# SmokeDetector.net
KiCad netlist of a schematic drawn in Altium Designer
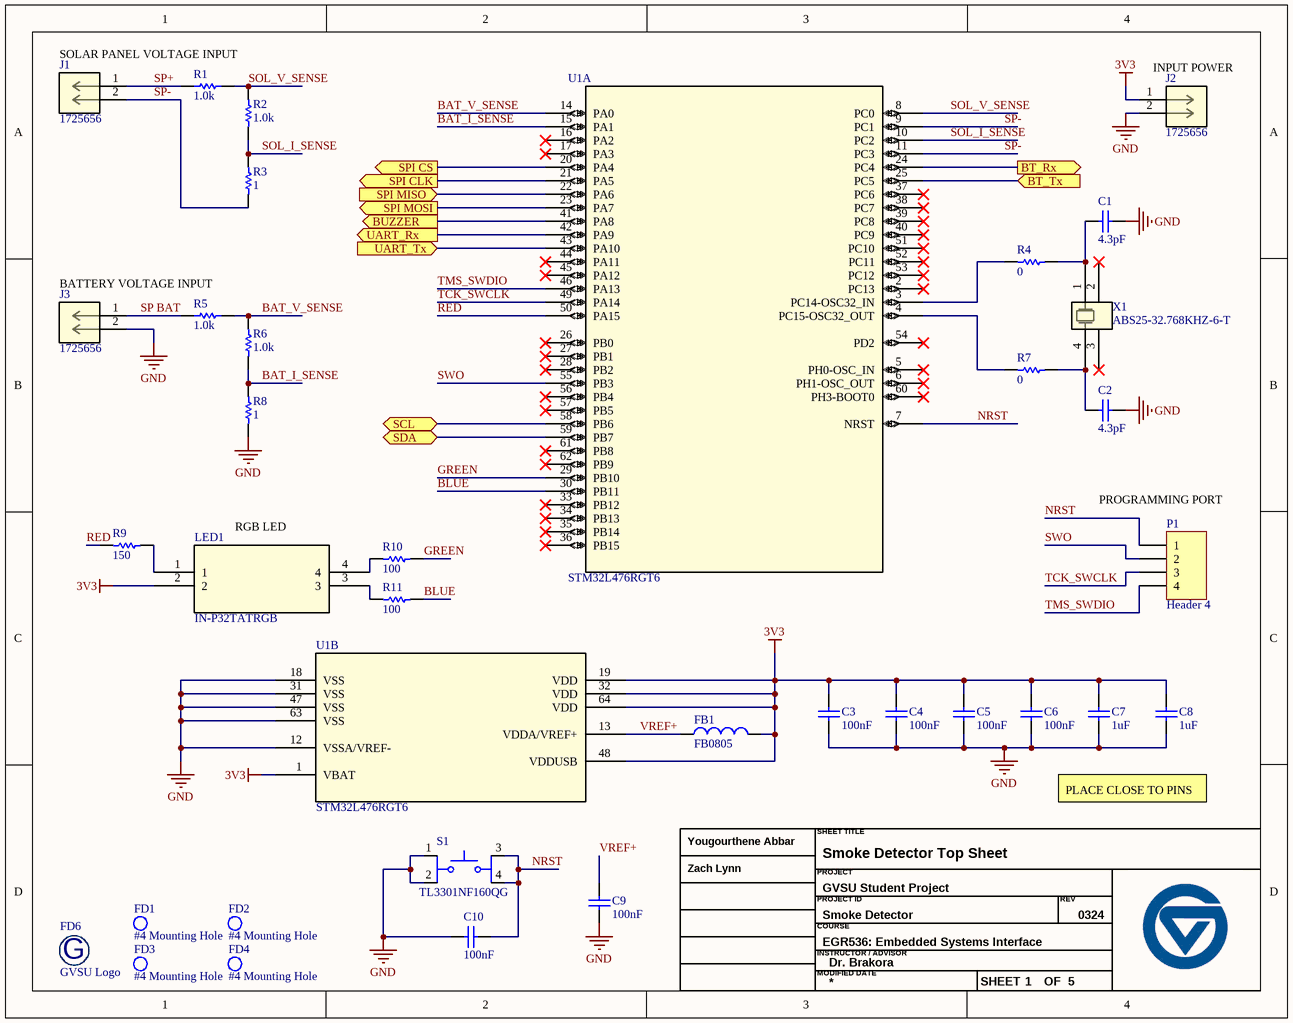
[diagram p0: SmokeDetector.SchDoc]

(export (version "E")
  (design (tool "Eeschema 10.0.6"))
  (components
    (comp (ref "C1")
      (value "4.3pF")
      (footprint "0402cap")
      (description "0402 Ceramic Chip Capacitor - Standard")
      (fields (field (name "Comment") "C0402"))
      (libsource (lib "Standard Components") (part "C0402"))
    )
    (comp (ref "C2")
      (value "4.3pF")
      (footprint "0402cap")
      (description "0402 Ceramic Chip Capacitor - Standard")
      (fields (field (name "Comment") "C0402"))
      (libsource (lib "Standard Components") (part "C0402"))
    )
    (comp (ref "C3")
      (value "100nF")
      (footprint "0402cap")
      (description "0402 Ceramic Chip Capacitor - Standard")
      (fields (field (name "Comment") "C0402"))
      (libsource (lib "Standard Components") (part "C0402"))
    )
    (comp (ref "C4")
      (value "100nF")
      (footprint "0402cap")
      (description "0402 Ceramic Chip Capacitor - Standard")
      (fields (field (name "Comment") "C0402"))
      (libsource (lib "Standard Components") (part "C0402"))
    )
    (comp (ref "C5")
      (value "100nF")
      (footprint "0402cap")
      (description "0402 Ceramic Chip Capacitor - Standard")
      (fields (field (name "Comment") "C0402"))
      (libsource (lib "Standard Components") (part "C0402"))
    )
    (comp (ref "C6")
      (value "100nF")
      (footprint "0402cap")
      (description "0402 Ceramic Chip Capacitor - Standard")
      (fields (field (name "Comment") "C0402"))
      (libsource (lib "Standard Components") (part "C0402"))
    )
    (comp (ref "C7")
      (value "1uF")
      (footprint "0402cap")
      (description "0402 Ceramic Chip Capacitor - Standard")
      (fields (field (name "Comment") "C0402"))
      (libsource (lib "Standard Components") (part "C0402"))
    )
    (comp (ref "C8")
      (value "1uF")
      (footprint "0805CAP")
      (description "0805 Ceramic Chip Capacitor - Standard")
      (fields (field (name "Comment") "C0805"))
      (libsource (lib "Standard Components") (part "C0805"))
    )
    (comp (ref "C9")
      (value "100nF")
      (footprint "0402cap")
      (description "0402 Ceramic Chip Capacitor - Standard")
      (fields (field (name "Comment") "C0402"))
      (libsource (lib "Standard Components") (part "C0402"))
    )
    (comp (ref "C10")
      (value "100nF")
      (footprint "0402cap")
      (description "0402 Ceramic Chip Capacitor - Standard")
      (fields (field (name "Comment") "C0402"))
      (libsource (lib "Standard Components") (part "C0402"))
    )
    (comp (ref "FB1")
      (value "FB0805")
      (footprint "0805CAP")
      (description "0805 Multilayer Ferrite Power Bead")
      (fields (field (name "MANUFACTURER") "KOA Speer"))
      (libsource (lib "Standard Components") (part "FB0805"))
    )
    (comp (ref "FD1")
      (value "#4 Mounting Hole")
      (footprint "#4 Mounting Hole-Footprint-1")
      (description "#4 clearance hole, unplated.")
      (libsource (lib "Standard Components") (part "#4 Mounting Hole"))
    )
    (comp (ref "FD2")
      (value "#4 Mounting Hole")
      (footprint "#4 Mounting Hole-Footprint-1")
      (description "#4 clearance hole, unplated.")
      (libsource (lib "Standard Components") (part "#4 Mounting Hole"))
    )
    (comp (ref "FD3")
      (value "#4 Mounting Hole")
      (footprint "#4 Mounting Hole-Footprint-1")
      (description "#4 clearance hole, unplated.")
      (libsource (lib "Standard Components") (part "#4 Mounting Hole"))
    )
    (comp (ref "FD4")
      (value "#4 Mounting Hole")
      (footprint "#4 Mounting Hole-Footprint-1")
      (description "#4 clearance hole, unplated.")
      (libsource (lib "Standard Components") (part "#4 Mounting Hole"))
    )
    (comp (ref "FD6")
      (value "GVSU Logo")
      (footprint "GVSU Symbol Only")
      (description "GVSU Logo (Several Symbols)")
      (libsource (lib "Standard Components") (part "GVSU Logo"))
    )
    (comp (ref "J1")
      (value "1725656")
      (footprint "CONN_1725656_PXC")
      (description "No Description Available")
      (libsource (lib "") (part "1725656_1"))
    )
    (comp (ref "J2")
      (value "1725656")
      (footprint "CONN_1725656_PXC")
      (description "No Description Available")
      (libsource (lib "ScrewTerminal2Position") (part "1725656"))
    )
    (comp (ref "J3")
      (value "1725656")
      (footprint "CONN_1725656_PXC")
      (description "No Description Available")
      (libsource (lib "") (part "1725656_1"))
    )
    (comp (ref "LED1")
      (value "IN-P32TATRGB")
      (footprint "4-PLCC_3P2X2P8_INL")
      (description "No Description Available")
      (libsource (lib "RGB") (part "IN-P32TATRGB"))
    )
    (comp (ref "P1")
      (value "Header 4")
      (footprint "HDR1X4")
      (description "Header, 4-Pin")
      (fields (field (name "PUBLISHER") "Altium Limited"))
      (libsource (lib "Miscellaneous Connectors") (part "Header 4"))
    )
    (comp (ref "R1")
      (value "1.0k")
      (footprint "0805RES")
      (description "0805 Chip Resistor - Standard")
      (fields (field (name "Comment") "R0805"))
      (libsource (lib "Standard Components") (part "R0805"))
    )
    (comp (ref "R2")
      (value "1.0k")
      (footprint "0805RES")
      (description "0805 Chip Resistor - Standard")
      (fields (field (name "Comment") "R0805"))
      (libsource (lib "Standard Components") (part "R0805"))
    )
    (comp (ref "R3")
      (value "1")
      (footprint "0805RES")
      (description "0805 Chip Resistor - Standard")
      (fields (field (name "Comment") "R0805"))
      (libsource (lib "Standard Components") (part "R0805"))
    )
    (comp (ref "R4")
      (value "0")
      (footprint "0402RES")
      (description "0402 Chip Resistor - Standard")
      (fields (field (name "Comment") "R0402"))
      (libsource (lib "Standard Components") (part "R0402"))
    )
    (comp (ref "R5")
      (value "1.0k")
      (footprint "0805RES")
      (description "0805 Chip Resistor - Standard")
      (fields (field (name "Comment") "R0805"))
      (libsource (lib "Standard Components") (part "R0805"))
    )
    (comp (ref "R6")
      (value "1.0k")
      (footprint "0805RES")
      (description "0805 Chip Resistor - Standard")
      (fields (field (name "Comment") "R0805"))
      (libsource (lib "Standard Components") (part "R0805"))
    )
    (comp (ref "R7")
      (value "0")
      (footprint "0402RES")
      (description "0402 Chip Resistor - Standard")
      (fields (field (name "Comment") "R0402"))
      (libsource (lib "Standard Components") (part "R0402"))
    )
    (comp (ref "R8")
      (value "1")
      (footprint "0805RES")
      (description "0805 Chip Resistor - Standard")
      (fields (field (name "Comment") "R0805"))
      (libsource (lib "Standard Components") (part "R0805"))
    )
    (comp (ref "R9")
      (value "150")
      (footprint "0805RES")
      (description "0805 Chip Resistor - Standard")
      (fields (field (name "Comment") "R0805"))
      (libsource (lib "Standard Components") (part "R0805"))
    )
    (comp (ref "R10")
      (value "100")
      (footprint "0805RES")
      (description "0805 Chip Resistor - Standard")
      (fields (field (name "Comment") "R0805"))
      (libsource (lib "Standard Components") (part "R0805"))
    )
    (comp (ref "R11")
      (value "100")
      (footprint "0805RES")
      (description "0805 Chip Resistor - Standard")
      (fields (field (name "Comment") "R0805"))
      (libsource (lib "Standard Components") (part "R0805"))
    )
    (comp (ref "S1")
      (value "TL3301NF160QG")
      (footprint "SW_TL3301NF160QG")
      (fields (field (name "MF") "{'manufacturer': u'E-Switch'}"))
      (libsource (lib "Button") (part "TL3301NF160QG"))
    )
    (comp (ref "U1")
      (value "STM32L476RGT6")
      (footprint "LQFP64-10x10mm_STM")
      (description "No Description Available")
      (fields (field (name "MANUFACTURER") "STMicroelectronics"))
      (libsource (lib "STM32L476RGT6") (part "STM32L476RGT6"))
    )
    (comp (ref "X1")
      (value "ABS25-32.768KHZ-6-T")
      (footprint "X_ABS25_ABR")
      (description "No Description Available")
      (libsource (lib "ABS25-32P768KHZ-6-T") (part "ABS25-32.768KHZ-6-T"))
    )
  )
  (nets
    (net (code "1") (name "/BAT_I_SENSE") (class "Default")
      (node (ref "R6") (pin "1") (pinfunction "1_1") (pintype "passive"))
      (node (ref "R8") (pin "2") (pinfunction "2_2") (pintype "passive"))
      (node (ref "U1") (pin "15") (pinfunction "PA1_15") (pintype "bidirectional"))
    )
    (net (code "2") (name "/BAT_V_SENSE") (class "Default")
      (node (ref "R5") (pin "1") (pinfunction "1_1") (pintype "passive"))
      (node (ref "R6") (pin "2") (pinfunction "2_2") (pintype "passive"))
      (node (ref "U1") (pin "14") (pinfunction "PA0_14") (pintype "bidirectional"))
    )
    (net (code "3") (name "/BLUE") (class "Default")
      (node (ref "R11") (pin "2") (pinfunction "2_2") (pintype "passive"))
      (node (ref "U1") (pin "30") (pinfunction "PB11_30") (pintype "bidirectional"))
    )
    (net (code "4") (name "/BT_Rx") (class "Default")
      (node (ref "U1") (pin "24") (pinfunction "PC4_24") (pintype "bidirectional"))
    )
    (net (code "5") (name "/BT_Tx") (class "Default")
      (node (ref "U1") (pin "25") (pinfunction "PC5_25") (pintype "bidirectional"))
    )
    (net (code "6") (name "/BUZZER") (class "Default")
      (node (ref "U1") (pin "41") (pinfunction "PA8_41") (pintype "bidirectional"))
    )
    (net (code "7") (name "/GREEN") (class "Default")
      (node (ref "R10") (pin "2") (pinfunction "2_2") (pintype "passive"))
      (node (ref "U1") (pin "29") (pinfunction "PB10_29") (pintype "bidirectional"))
    )
    (net (code "8") (name "/NRST") (class "Default")
      (node (ref "C10") (pin "2") (pinfunction "2_2") (pintype "passive"))
      (node (ref "P1") (pin "1") (pinfunction "1_1") (pintype "passive"))
      (node (ref "S1") (pin "3") (pinfunction "3_3") (pintype "passive"))
      (node (ref "S1") (pin "4") (pinfunction "4_4") (pintype "passive"))
      (node (ref "U1") (pin "7") (pinfunction "NRST_7") (pintype "bidirectional"))
    )
    (net (code "9") (name "/RED") (class "Default")
      (node (ref "R9") (pin "1") (pinfunction "1_1") (pintype "passive"))
      (node (ref "U1") (pin "50") (pinfunction "PA15_50") (pintype "bidirectional"))
    )
    (net (code "10") (name "/SCL") (class "Default")
      (node (ref "U1") (pin "58") (pinfunction "PB6_58") (pintype "bidirectional"))
    )
    (net (code "11") (name "/SDA") (class "Default")
      (node (ref "U1") (pin "59") (pinfunction "PB7_59") (pintype "bidirectional"))
    )
    (net (code "12") (name "/SOL_I_SENSE") (class "Default")
      (node (ref "R2") (pin "1") (pinfunction "1_1") (pintype "passive"))
      (node (ref "R3") (pin "2") (pinfunction "2_2") (pintype "passive"))
      (node (ref "U1") (pin "10") (pinfunction "PC2_10") (pintype "bidirectional"))
    )
    (net (code "13") (name "/SOL_V_SENSE") (class "Default")
      (node (ref "R1") (pin "1") (pinfunction "1_1") (pintype "passive"))
      (node (ref "R2") (pin "2") (pinfunction "2_2") (pintype "passive"))
      (node (ref "U1") (pin "8") (pinfunction "PC0_8") (pintype "bidirectional"))
    )
    (net (code "14") (name "/SP BAT") (class "Default")
      (node (ref "J3") (pin "1") (pinfunction "1_1") (pintype "passive"))
      (node (ref "R5") (pin "2") (pinfunction "2_2") (pintype "passive"))
    )
    (net (code "15") (name "/SP+") (class "Default")
      (node (ref "J1") (pin "1") (pinfunction "1_1") (pintype "passive"))
      (node (ref "R1") (pin "2") (pinfunction "2_2") (pintype "passive"))
    )
    (net (code "16") (name "/SP-") (class "Default")
      (node (ref "J1") (pin "2") (pinfunction "2_2") (pintype "passive"))
      (node (ref "R3") (pin "1") (pinfunction "1_1") (pintype "passive"))
      (node (ref "U1") (pin "11") (pinfunction "PC3_11") (pintype "bidirectional"))
      (node (ref "U1") (pin "9") (pinfunction "PC1_9") (pintype "bidirectional"))
    )
    (net (code "17") (name "/SPI CLK") (class "Default")
      (node (ref "U1") (pin "21") (pinfunction "PA5_21") (pintype "bidirectional"))
    )
    (net (code "18") (name "/SPI CS") (class "Default")
      (node (ref "U1") (pin "20") (pinfunction "PA4_20") (pintype "bidirectional"))
    )
    (net (code "19") (name "/SPI MISO") (class "Default")
      (node (ref "U1") (pin "22") (pinfunction "PA6_22") (pintype "bidirectional"))
    )
    (net (code "20") (name "/SPI MOSI") (class "Default")
      (node (ref "U1") (pin "23") (pinfunction "PA7_23") (pintype "bidirectional"))
    )
    (net (code "21") (name "/SWO") (class "Default")
      (node (ref "P1") (pin "2") (pinfunction "2_2") (pintype "passive"))
      (node (ref "U1") (pin "55") (pinfunction "PB3_55") (pintype "bidirectional"))
    )
    (net (code "22") (name "/TCK_SWCLK") (class "Default")
      (node (ref "P1") (pin "3") (pinfunction "3_3") (pintype "passive"))
      (node (ref "U1") (pin "49") (pinfunction "PA14_49") (pintype "bidirectional"))
    )
    (net (code "23") (name "/TMS_SWDIO") (class "Default")
      (node (ref "P1") (pin "4") (pinfunction "4_4") (pintype "passive"))
      (node (ref "U1") (pin "46") (pinfunction "PA13_46") (pintype "bidirectional"))
    )
    (net (code "24") (name "/UART_Rx") (class "Default")
      (node (ref "U1") (pin "42") (pinfunction "PA9_42") (pintype "bidirectional"))
    )
    (net (code "25") (name "/UART_Tx") (class "Default")
      (node (ref "U1") (pin "43") (pinfunction "PA10_43") (pintype "bidirectional"))
    )
    (net (code "26") (name "/VREF+") (class "Default")
      (node (ref "C9") (pin "2") (pinfunction "2_2") (pintype "passive"))
      (node (ref "FB1") (pin "1") (pinfunction "1_1") (pintype "passive"))
      (node (ref "U1") (pin "13") (pinfunction "VDDA/VREF+_13") (pintype "power_in"))
    )
    (net (code "27") (name "3V3") (class "Default")
      (node (ref "C3") (pin "2") (pinfunction "2_2") (pintype "passive"))
      (node (ref "C4") (pin "2") (pinfunction "2_2") (pintype "passive"))
      (node (ref "C5") (pin "2") (pinfunction "2_2") (pintype "passive"))
      (node (ref "C6") (pin "2") (pinfunction "2_2") (pintype "passive"))
      (node (ref "C7") (pin "2") (pinfunction "2_2") (pintype "passive"))
      (node (ref "C8") (pin "2") (pinfunction "2_2") (pintype "passive"))
      (node (ref "FB1") (pin "2") (pinfunction "2_2") (pintype "passive"))
      (node (ref "J2") (pin "1") (pinfunction "1_1") (pintype "passive"))
      (node (ref "LED1") (pin "2") (pinfunction "2_2") (pintype "passive"))
      (node (ref "U1") (pin "1") (pinfunction "VBAT_1") (pintype "power_in"))
      (node (ref "U1") (pin "19") (pinfunction "VDD_19") (pintype "power_in"))
      (node (ref "U1") (pin "32") (pinfunction "VDD_32") (pintype "power_in"))
      (node (ref "U1") (pin "48") (pinfunction "VDDUSB_48") (pintype "power_in"))
      (node (ref "U1") (pin "64") (pinfunction "VDD_64") (pintype "power_in"))
    )
    (net (code "28") (name "GND") (class "Default")
      (node (ref "C1") (pin "2") (pinfunction "2_2") (pintype "passive"))
      (node (ref "C10") (pin "1") (pinfunction "1_1") (pintype "passive"))
      (node (ref "C2") (pin "2") (pinfunction "2_2") (pintype "passive"))
      (node (ref "C3") (pin "1") (pinfunction "1_1") (pintype "passive"))
      (node (ref "C4") (pin "1") (pinfunction "1_1") (pintype "passive"))
      (node (ref "C5") (pin "1") (pinfunction "1_1") (pintype "passive"))
      (node (ref "C6") (pin "1") (pinfunction "1_1") (pintype "passive"))
      (node (ref "C7") (pin "1") (pinfunction "1_1") (pintype "passive"))
      (node (ref "C8") (pin "1") (pinfunction "1_1") (pintype "passive"))
      (node (ref "C9") (pin "1") (pinfunction "1_1") (pintype "passive"))
      (node (ref "J2") (pin "2") (pinfunction "2_2") (pintype "passive"))
      (node (ref "J3") (pin "2") (pinfunction "2_2") (pintype "passive"))
      (node (ref "R8") (pin "1") (pinfunction "1_1") (pintype "passive"))
      (node (ref "S1") (pin "1") (pinfunction "1_1") (pintype "passive"))
      (node (ref "S1") (pin "2") (pinfunction "2_2") (pintype "passive"))
      (node (ref "U1") (pin "12") (pinfunction "VSSA/VREF-_12") (pintype "power_in"))
      (node (ref "U1") (pin "18") (pinfunction "VSS_18") (pintype "power_in"))
      (node (ref "U1") (pin "31") (pinfunction "VSS_31") (pintype "power_in"))
      (node (ref "U1") (pin "47") (pinfunction "VSS_47") (pintype "power_in"))
      (node (ref "U1") (pin "63") (pinfunction "VSS_63") (pintype "power_in"))
    )
    (net (code "29") (name "Net-(C1-Pad1)") (class "Default")
      (node (ref "C1") (pin "1") (pinfunction "1_1") (pintype "passive"))
      (node (ref "R4") (pin "2") (pinfunction "2_2") (pintype "passive"))
      (node (ref "X1") (pin "1") (pinfunction "CRYSTAL_1") (pintype "passive"))
    )
    (net (code "30") (name "Net-(C2-Pad1)") (class "Default")
      (node (ref "C2") (pin "1") (pinfunction "1_1") (pintype "passive"))
      (node (ref "R7") (pin "2") (pinfunction "2_2") (pintype "passive"))
      (node (ref "X1") (pin "4") (pinfunction "CRYSTAL_4") (pintype "passive"))
    )
    (net (code "31") (name "Net-(LED1-Pad1)") (class "Default")
      (node (ref "LED1") (pin "1") (pinfunction "1_1") (pintype "passive"))
      (node (ref "R9") (pin "2") (pinfunction "2_2") (pintype "passive"))
    )
    (net (code "32") (name "Net-(LED1-Pad3)") (class "Default")
      (node (ref "LED1") (pin "3") (pinfunction "3_3") (pintype "passive"))
      (node (ref "R11") (pin "1") (pinfunction "1_1") (pintype "passive"))
    )
    (net (code "33") (name "Net-(LED1-Pad4)") (class "Default")
      (node (ref "LED1") (pin "4") (pinfunction "4_4") (pintype "passive"))
      (node (ref "R10") (pin "1") (pinfunction "1_1") (pintype "passive"))
    )
    (net (code "34") (name "Net-(U1A-PC14-OSC32_IN)") (class "Default")
      (node (ref "R4") (pin "1") (pinfunction "1_1") (pintype "passive"))
      (node (ref "U1") (pin "3") (pinfunction "PC14-OSC32_IN_3") (pintype "bidirectional"))
    )
    (net (code "35") (name "Net-(U1A-PC15-OSC32_OUT)") (class "Default")
      (node (ref "R7") (pin "1") (pinfunction "1_1") (pintype "passive"))
      (node (ref "U1") (pin "4") (pinfunction "PC15-OSC32_OUT_4") (pintype "bidirectional"))
    )
    (net (code "36") (name "unconnected-(U1A-PA2-Pad16)") (class "Default")
      (node (ref "U1") (pin "16") (pinfunction "PA2_16") (pintype "bidirectional+no_connect"))
    )
    (net (code "37") (name "unconnected-(U1A-PA3-Pad17)") (class "Default")
      (node (ref "U1") (pin "17") (pinfunction "PA3_17") (pintype "bidirectional+no_connect"))
    )
    (net (code "38") (name "unconnected-(U1A-PA11-Pad44)") (class "Default")
      (node (ref "U1") (pin "44") (pinfunction "PA11_44") (pintype "bidirectional+no_connect"))
    )
    (net (code "39") (name "unconnected-(U1A-PA12-Pad45)") (class "Default")
      (node (ref "U1") (pin "45") (pinfunction "PA12_45") (pintype "bidirectional+no_connect"))
    )
    (net (code "40") (name "unconnected-(U1A-PB0-Pad26)") (class "Default")
      (node (ref "U1") (pin "26") (pinfunction "PB0_26") (pintype "bidirectional+no_connect"))
    )
    (net (code "41") (name "unconnected-(U1A-PB1-Pad27)") (class "Default")
      (node (ref "U1") (pin "27") (pinfunction "PB1_27") (pintype "bidirectional+no_connect"))
    )
    (net (code "42") (name "unconnected-(U1A-PB2-Pad28)") (class "Default")
      (node (ref "U1") (pin "28") (pinfunction "PB2_28") (pintype "bidirectional+no_connect"))
    )
    (net (code "43") (name "unconnected-(U1A-PB4-Pad56)") (class "Default")
      (node (ref "U1") (pin "56") (pinfunction "PB4_56") (pintype "bidirectional+no_connect"))
    )
    (net (code "44") (name "unconnected-(U1A-PB5-Pad57)") (class "Default")
      (node (ref "U1") (pin "57") (pinfunction "PB5_57") (pintype "bidirectional+no_connect"))
    )
    (net (code "45") (name "unconnected-(U1A-PB8-Pad61)") (class "Default")
      (node (ref "U1") (pin "61") (pinfunction "PB8_61") (pintype "bidirectional+no_connect"))
    )
    (net (code "46") (name "unconnected-(U1A-PB9-Pad62)") (class "Default")
      (node (ref "U1") (pin "62") (pinfunction "PB9_62") (pintype "bidirectional+no_connect"))
    )
    (net (code "47") (name "unconnected-(U1A-PB12-Pad33)") (class "Default")
      (node (ref "U1") (pin "33") (pinfunction "PB12_33") (pintype "bidirectional+no_connect"))
    )
    (net (code "48") (name "unconnected-(U1A-PB13-Pad34)") (class "Default")
      (node (ref "U1") (pin "34") (pinfunction "PB13_34") (pintype "bidirectional+no_connect"))
    )
    (net (code "49") (name "unconnected-(U1A-PB14-Pad35)") (class "Default")
      (node (ref "U1") (pin "35") (pinfunction "PB14_35") (pintype "bidirectional+no_connect"))
    )
    (net (code "50") (name "unconnected-(U1A-PB15-Pad36)") (class "Default")
      (node (ref "U1") (pin "36") (pinfunction "PB15_36") (pintype "bidirectional+no_connect"))
    )
    (net (code "51") (name "unconnected-(U1A-PC6-Pad37)") (class "Default")
      (node (ref "U1") (pin "37") (pinfunction "PC6_37") (pintype "bidirectional+no_connect"))
    )
    (net (code "52") (name "unconnected-(U1A-PC7-Pad38)") (class "Default")
      (node (ref "U1") (pin "38") (pinfunction "PC7_38") (pintype "bidirectional+no_connect"))
    )
    (net (code "53") (name "unconnected-(U1A-PC8-Pad39)") (class "Default")
      (node (ref "U1") (pin "39") (pinfunction "PC8_39") (pintype "bidirectional+no_connect"))
    )
    (net (code "54") (name "unconnected-(U1A-PC9-Pad40)") (class "Default")
      (node (ref "U1") (pin "40") (pinfunction "PC9_40") (pintype "bidirectional+no_connect"))
    )
    (net (code "55") (name "unconnected-(U1A-PC10-Pad51)") (class "Default")
      (node (ref "U1") (pin "51") (pinfunction "PC10_51") (pintype "bidirectional+no_connect"))
    )
    (net (code "56") (name "unconnected-(U1A-PC11-Pad52)") (class "Default")
      (node (ref "U1") (pin "52") (pinfunction "PC11_52") (pintype "bidirectional+no_connect"))
    )
    (net (code "57") (name "unconnected-(U1A-PC12-Pad53)") (class "Default")
      (node (ref "U1") (pin "53") (pinfunction "PC12_53") (pintype "bidirectional+no_connect"))
    )
    (net (code "58") (name "unconnected-(U1A-PC13-Pad2)") (class "Default")
      (node (ref "U1") (pin "2") (pinfunction "PC13_2") (pintype "bidirectional+no_connect"))
    )
    (net (code "59") (name "unconnected-(U1A-PD2-Pad54)") (class "Default")
      (node (ref "U1") (pin "54") (pinfunction "PD2_54") (pintype "bidirectional+no_connect"))
    )
    (net (code "60") (name "unconnected-(U1A-PH0-OSC_IN-Pad5)") (class "Default")
      (node (ref "U1") (pin "5") (pinfunction "PH0-OSC_IN_5") (pintype "bidirectional+no_connect"))
    )
    (net (code "61") (name "unconnected-(U1A-PH1-OSC_OUT-Pad6)") (class "Default")
      (node (ref "U1") (pin "6") (pinfunction "PH1-OSC_OUT_6") (pintype "bidirectional+no_connect"))
    )
    (net (code "62") (name "unconnected-(U1A-PH3-BOOT0-Pad60)") (class "Default")
      (node (ref "U1") (pin "60") (pinfunction "PH3-BOOT0_60") (pintype "bidirectional+no_connect"))
    )
    (net (code "63") (name "unconnected-(X1-NC-Pad2)") (class "Default")
      (node (ref "X1") (pin "2") (pinfunction "NC_2") (pintype "passive+no_connect"))
    )
    (net (code "64") (name "unconnected-(X1-NC-Pad3)") (class "Default")
      (node (ref "X1") (pin "3") (pinfunction "NC_3") (pintype "passive+no_connect"))
    )
  )
)
